# 2002_Capteur_Indication.net
KiCad netlist of a schematic drawn in Altium Designer
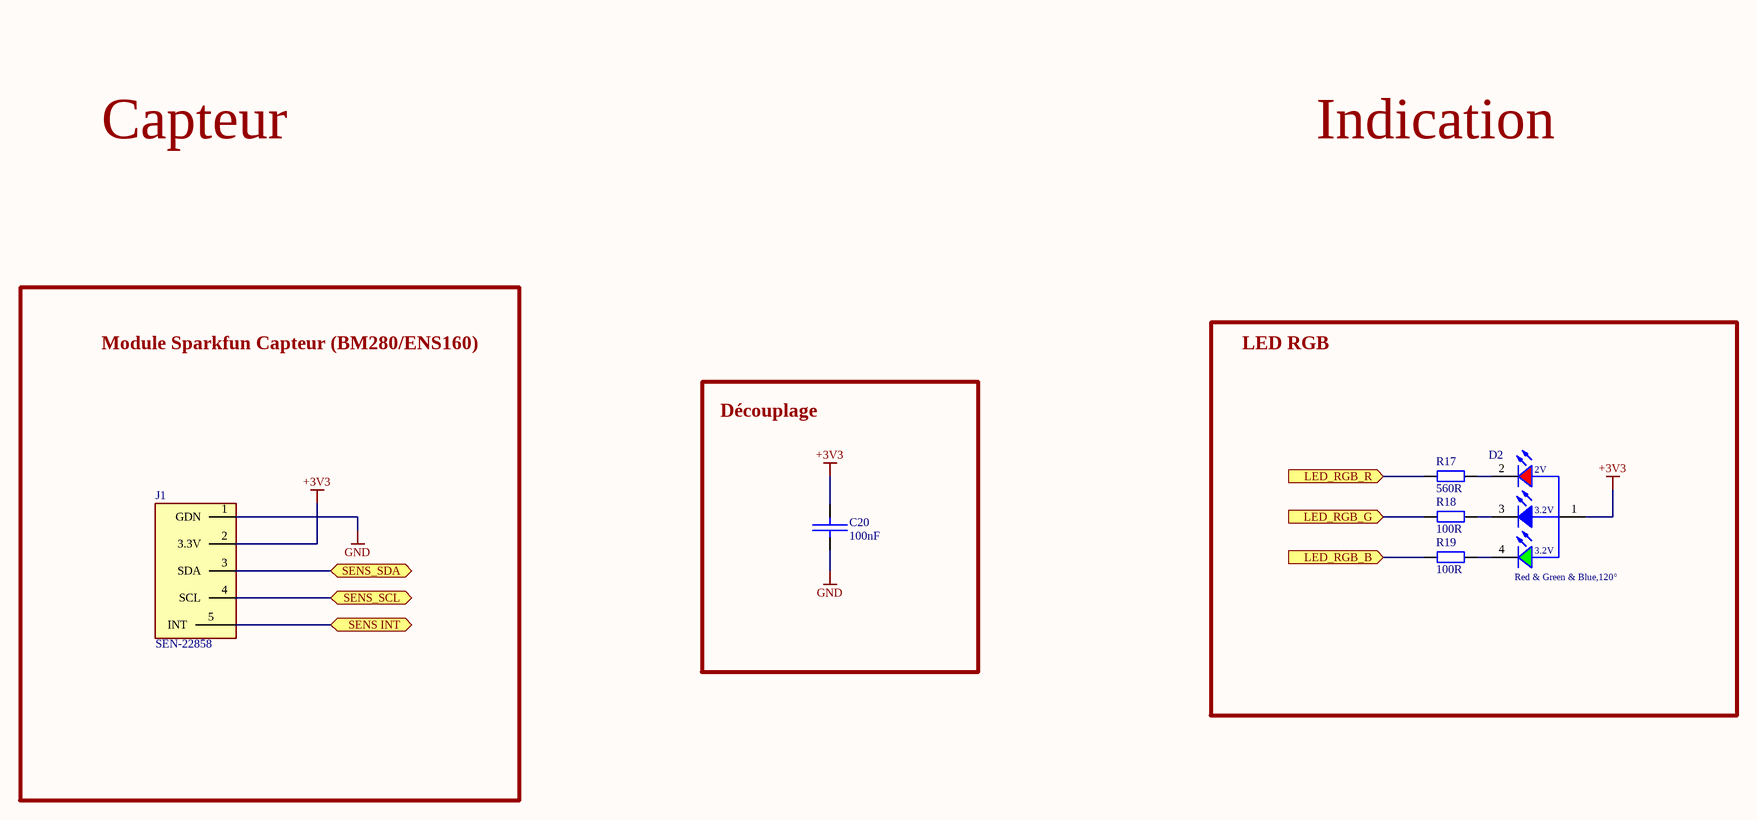
[diagram p0: 2002_Capteur_Indication.SchDoc]

(export (version "E")
  (design (tool "Eeschema 10.0.6"))
  (components
    (comp (ref "C20")
      (value "100nF")
      (footprint "0805")
      (description "Capacitor smd")
      (libsource (lib "2002_CapteurMeteoWifi") (part "Condensator"))
    )
    (comp (ref "D2")
      (value "Red & Green & Blue,120°")
      (footprint "LED_APHF1608LSEEQBDZGKC")
      (description "DEL standard - CMS RGB 0603 SMD")
      (fields (field (name "PART NUMBER") "150066M153000") (field (name "PUBLISHER") "Wurth Elektronik"))
      (libsource (lib "Schlib1") (part "APHF1608LSEEQBDZGKC"))
    )
    (comp (ref "J1")
      (value "SEN-22858")
      (footprint "SEN-22858")
      (description "BME280/ENS160")
      (fields
        (field (name "MOUSER2 PART NUMBER") "649-68604-804HLF")
        (field (name "MANUFACTURER_PART_NUMBER") "68604-804HLF")
      )
      (libsource (lib "Schlib1") (part "BME280/ENS160"))
    )
    (comp (ref "R17")
      (value "560R")
      (footprint "0805")
      (description "SMD Resistor")
      (fields (field (name "RESISTANCE") "560R"))
      (libsource (lib "2312-MS-0805") (part "RES-0805"))
    )
    (comp (ref "R18")
      (value "100R")
      (footprint "0805")
      (description "SMD Resistor")
      (fields (field (name "RESISTANCE") "100R"))
      (libsource (lib "2312-MS-0805") (part "RES-0805"))
    )
    (comp (ref "R19")
      (value "100R")
      (footprint "0805")
      (description "SMD Resistor")
      (fields (field (name "RESISTANCE") "100R"))
      (libsource (lib "2312-MS-0805") (part "RES-0805"))
    )
  )
  (nets
    (net (code "1") (name "+3V3") (class "Default")
      (node (ref "C20") (pin "1") (pinfunction "1_1") (pintype "passive"))
      (node (ref "D2") (pin "1") (pinfunction "1_1") (pintype "passive"))
      (node (ref "J1") (pin "2") (pinfunction "3.3V_2") (pintype "passive"))
    )
    (net (code "2") (name "/LED_RGB_B") (class "Default")
      (node (ref "R19") (pin "1") (pinfunction "1_1") (pintype "passive"))
    )
    (net (code "3") (name "/LED_RGB_G") (class "Default")
      (node (ref "R18") (pin "1") (pinfunction "1_1") (pintype "passive"))
    )
    (net (code "4") (name "/LED_RGB_R") (class "Default")
      (node (ref "R17") (pin "1") (pinfunction "1_1") (pintype "passive"))
    )
    (net (code "5") (name "/SENS INT") (class "Default")
      (node (ref "J1") (pin "5") (pinfunction "INT_5") (pintype "passive"))
    )
    (net (code "6") (name "/SENS_SCL") (class "Default")
      (node (ref "J1") (pin "4") (pinfunction "SCL_4") (pintype "passive"))
    )
    (net (code "7") (name "/SENS_SDA") (class "Default")
      (node (ref "J1") (pin "3") (pinfunction "SDA_3") (pintype "passive"))
    )
    (net (code "8") (name "GND") (class "Default")
      (node (ref "C20") (pin "2") (pinfunction "2_2") (pintype "passive"))
      (node (ref "J1") (pin "1") (pinfunction "GDN_1") (pintype "passive"))
    )
    (net (code "9") (name "Net-(D2-BLUE)") (class "Default")
      (node (ref "D2") (pin "3") (pinfunction "BLUE_3") (pintype "passive"))
      (node (ref "R18") (pin "2") (pinfunction "2_2") (pintype "passive"))
    )
    (net (code "10") (name "Net-(D2-GREEN)") (class "Default")
      (node (ref "D2") (pin "4") (pinfunction "GREEN_4") (pintype "passive"))
      (node (ref "R19") (pin "2") (pinfunction "2_2") (pintype "passive"))
    )
    (net (code "11") (name "Net-(D2-RED)") (class "Default")
      (node (ref "D2") (pin "2") (pinfunction "RED_2") (pintype "passive"))
      (node (ref "R17") (pin "2") (pinfunction "2_2") (pintype "passive"))
    )
  )
)
